# keys.net
KiCad netlist of a schematic drawn in Altium Designer
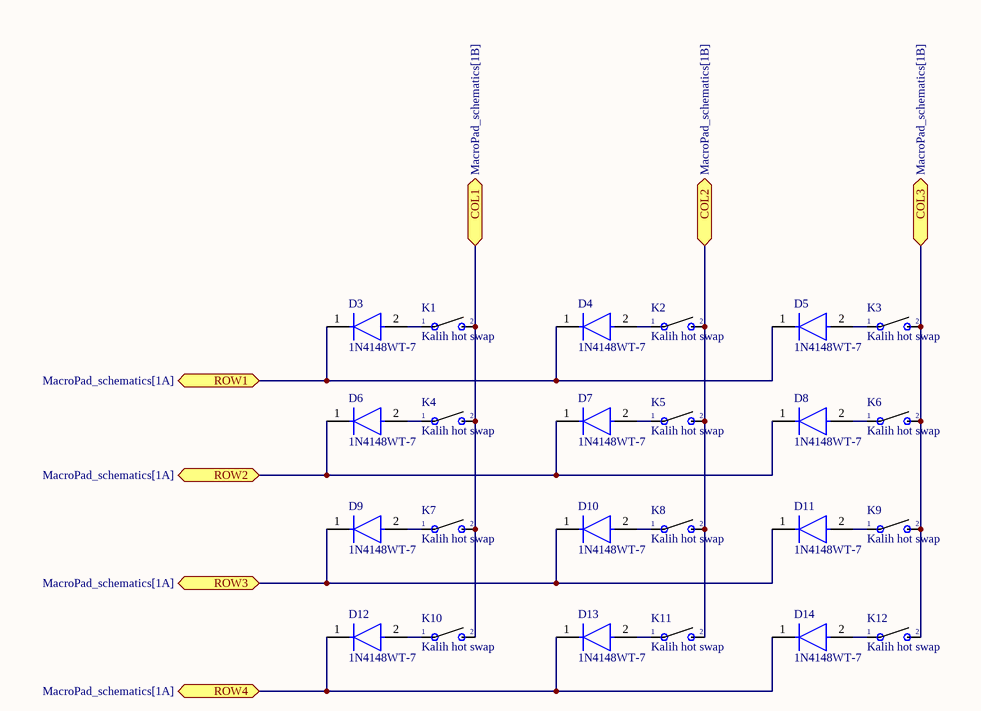
[diagram p0: keys.SchDoc]

(export (version "E")
  (design (tool "Eeschema 10.0.6"))
  (components
    (comp (ref "D3")
      (value "1N4148WT-7")
      (footprint "FP-SOD523-MFG")
      (description "DIODE GEN PURP 80V 125MA SOD523")
      (libsource (lib "Altium Content Vault") (part "d7152d700b627762746794eb795d46e"))
    )
    (comp (ref "D4")
      (value "1N4148WT-7")
      (footprint "FP-SOD523-MFG")
      (description "DIODE GEN PURP 80V 125MA SOD523")
      (libsource (lib "Altium Content Vault") (part "d7152d700b627762746794eb795d46e"))
    )
    (comp (ref "D5")
      (value "1N4148WT-7")
      (footprint "FP-SOD523-MFG")
      (description "DIODE GEN PURP 80V 125MA SOD523")
      (libsource (lib "Altium Content Vault") (part "d7152d700b627762746794eb795d46e"))
    )
    (comp (ref "D6")
      (value "1N4148WT-7")
      (footprint "FP-SOD523-MFG")
      (description "DIODE GEN PURP 80V 125MA SOD523")
      (libsource (lib "Altium Content Vault") (part "d7152d700b627762746794eb795d46e"))
    )
    (comp (ref "D7")
      (value "1N4148WT-7")
      (footprint "FP-SOD523-MFG")
      (description "DIODE GEN PURP 80V 125MA SOD523")
      (libsource (lib "Altium Content Vault") (part "d7152d700b627762746794eb795d46e"))
    )
    (comp (ref "D8")
      (value "1N4148WT-7")
      (footprint "FP-SOD523-MFG")
      (description "DIODE GEN PURP 80V 125MA SOD523")
      (libsource (lib "Altium Content Vault") (part "d7152d700b627762746794eb795d46e"))
    )
    (comp (ref "D9")
      (value "1N4148WT-7")
      (footprint "FP-SOD523-MFG")
      (description "DIODE GEN PURP 80V 125MA SOD523")
      (libsource (lib "Altium Content Vault") (part "d7152d700b627762746794eb795d46e"))
    )
    (comp (ref "D10")
      (value "1N4148WT-7")
      (footprint "FP-SOD523-MFG")
      (description "DIODE GEN PURP 80V 125MA SOD523")
      (libsource (lib "Altium Content Vault") (part "d7152d700b627762746794eb795d46e"))
    )
    (comp (ref "D11")
      (value "1N4148WT-7")
      (footprint "FP-SOD523-MFG")
      (description "DIODE GEN PURP 80V 125MA SOD523")
      (libsource (lib "Altium Content Vault") (part "d7152d700b627762746794eb795d46e"))
    )
    (comp (ref "D12")
      (value "1N4148WT-7")
      (footprint "FP-SOD523-MFG")
      (description "DIODE GEN PURP 80V 125MA SOD523")
      (libsource (lib "Altium Content Vault") (part "d7152d700b627762746794eb795d46e"))
    )
    (comp (ref "D13")
      (value "1N4148WT-7")
      (footprint "FP-SOD523-MFG")
      (description "DIODE GEN PURP 80V 125MA SOD523")
      (libsource (lib "Altium Content Vault") (part "d7152d700b627762746794eb795d46e"))
    )
    (comp (ref "D14")
      (value "1N4148WT-7")
      (footprint "FP-SOD523-MFG")
      (description "DIODE GEN PURP 80V 125MA SOD523")
      (libsource (lib "Altium Content Vault") (part "d7152d700b627762746794eb795d46e"))
    )
    (comp (ref "K1")
      (value "Kalih hot swap")
      (footprint "Kailh_socket_MX_optional_reversible")
      (libsource (lib "MacroPad_schematicsLibrary") (part "Kalih hot swap"))
    )
    (comp (ref "K2")
      (value "Kalih hot swap")
      (footprint "Kailh_socket_MX_optional_reversible")
      (libsource (lib "MacroPad_schematicsLibrary") (part "Kalih hot swap"))
    )
    (comp (ref "K3")
      (value "Kalih hot swap")
      (footprint "Kailh_socket_MX_optional_reversible")
      (libsource (lib "MacroPad_schematicsLibrary") (part "Kalih hot swap"))
    )
    (comp (ref "K4")
      (value "Kalih hot swap")
      (footprint "Kailh_socket_MX_optional_reversible")
      (libsource (lib "MacroPad_schematicsLibrary") (part "Kalih hot swap"))
    )
    (comp (ref "K5")
      (value "Kalih hot swap")
      (footprint "Kailh_socket_MX_optional_reversible")
      (libsource (lib "MacroPad_schematicsLibrary") (part "Kalih hot swap"))
    )
    (comp (ref "K6")
      (value "Kalih hot swap")
      (footprint "Kailh_socket_MX_optional_reversible")
      (libsource (lib "MacroPad_schematicsLibrary") (part "Kalih hot swap"))
    )
    (comp (ref "K7")
      (value "Kalih hot swap")
      (footprint "Kailh_socket_MX_optional_reversible")
      (libsource (lib "MacroPad_schematicsLibrary") (part "Kalih hot swap"))
    )
    (comp (ref "K8")
      (value "Kalih hot swap")
      (footprint "Kailh_socket_MX_optional_reversible")
      (libsource (lib "MacroPad_schematicsLibrary") (part "Kalih hot swap"))
    )
    (comp (ref "K9")
      (value "Kalih hot swap")
      (footprint "Kailh_socket_MX_optional_reversible")
      (libsource (lib "MacroPad_schematicsLibrary") (part "Kalih hot swap"))
    )
    (comp (ref "K10")
      (value "Kalih hot swap")
      (footprint "Kailh_socket_MX_optional_reversible")
      (libsource (lib "MacroPad_schematicsLibrary") (part "Kalih hot swap"))
    )
    (comp (ref "K11")
      (value "Kalih hot swap")
      (footprint "Kailh_socket_MX_optional_reversible")
      (libsource (lib "MacroPad_schematicsLibrary") (part "Kalih hot swap"))
    )
    (comp (ref "K12")
      (value "Kalih hot swap")
      (footprint "Kailh_socket_MX_optional_reversible")
      (libsource (lib "MacroPad_schematicsLibrary") (part "Kalih hot swap"))
    )
  )
  (nets
    (net (code "1") (name "/COL1") (class "Default")
      (node (ref "K1") (pin "2") (pinfunction "2_2") (pintype "passive"))
      (node (ref "K10") (pin "2") (pinfunction "2_2") (pintype "passive"))
      (node (ref "K4") (pin "2") (pinfunction "2_2") (pintype "passive"))
      (node (ref "K7") (pin "2") (pinfunction "2_2") (pintype "passive"))
    )
    (net (code "2") (name "/COL2") (class "Default")
      (node (ref "K11") (pin "2") (pinfunction "2_2") (pintype "passive"))
      (node (ref "K2") (pin "2") (pinfunction "2_2") (pintype "passive"))
      (node (ref "K5") (pin "2") (pinfunction "2_2") (pintype "passive"))
      (node (ref "K8") (pin "2") (pinfunction "2_2") (pintype "passive"))
    )
    (net (code "3") (name "/COL3") (class "Default")
      (node (ref "K12") (pin "2") (pinfunction "2_2") (pintype "passive"))
      (node (ref "K3") (pin "2") (pinfunction "2_2") (pintype "passive"))
      (node (ref "K6") (pin "2") (pinfunction "2_2") (pintype "passive"))
      (node (ref "K9") (pin "2") (pinfunction "2_2") (pintype "passive"))
    )
    (net (code "4") (name "/ROW1") (class "Default")
      (node (ref "D3") (pin "1") (pinfunction "C_1") (pintype "passive"))
      (node (ref "D4") (pin "1") (pinfunction "C_1") (pintype "passive"))
      (node (ref "D5") (pin "1") (pinfunction "C_1") (pintype "passive"))
    )
    (net (code "5") (name "/ROW2") (class "Default")
      (node (ref "D6") (pin "1") (pinfunction "C_1") (pintype "passive"))
      (node (ref "D7") (pin "1") (pinfunction "C_1") (pintype "passive"))
      (node (ref "D8") (pin "1") (pinfunction "C_1") (pintype "passive"))
    )
    (net (code "6") (name "/ROW3") (class "Default")
      (node (ref "D10") (pin "1") (pinfunction "C_1") (pintype "passive"))
      (node (ref "D11") (pin "1") (pinfunction "C_1") (pintype "passive"))
      (node (ref "D9") (pin "1") (pinfunction "C_1") (pintype "passive"))
    )
    (net (code "7") (name "/ROW4") (class "Default")
      (node (ref "D12") (pin "1") (pinfunction "C_1") (pintype "passive"))
      (node (ref "D13") (pin "1") (pinfunction "C_1") (pintype "passive"))
      (node (ref "D14") (pin "1") (pinfunction "C_1") (pintype "passive"))
    )
    (net (code "8") (name "Net-(D3-A)") (class "Default")
      (node (ref "D3") (pin "2") (pinfunction "A_2") (pintype "passive"))
      (node (ref "K1") (pin "1") (pinfunction "1_1") (pintype "passive"))
    )
    (net (code "9") (name "Net-(D4-A)") (class "Default")
      (node (ref "D4") (pin "2") (pinfunction "A_2") (pintype "passive"))
      (node (ref "K2") (pin "1") (pinfunction "1_1") (pintype "passive"))
    )
    (net (code "10") (name "Net-(D5-A)") (class "Default")
      (node (ref "D5") (pin "2") (pinfunction "A_2") (pintype "passive"))
      (node (ref "K3") (pin "1") (pinfunction "1_1") (pintype "passive"))
    )
    (net (code "11") (name "Net-(D6-A)") (class "Default")
      (node (ref "D6") (pin "2") (pinfunction "A_2") (pintype "passive"))
      (node (ref "K4") (pin "1") (pinfunction "1_1") (pintype "passive"))
    )
    (net (code "12") (name "Net-(D7-A)") (class "Default")
      (node (ref "D7") (pin "2") (pinfunction "A_2") (pintype "passive"))
      (node (ref "K5") (pin "1") (pinfunction "1_1") (pintype "passive"))
    )
    (net (code "13") (name "Net-(D8-A)") (class "Default")
      (node (ref "D8") (pin "2") (pinfunction "A_2") (pintype "passive"))
      (node (ref "K6") (pin "1") (pinfunction "1_1") (pintype "passive"))
    )
    (net (code "14") (name "Net-(D9-A)") (class "Default")
      (node (ref "D9") (pin "2") (pinfunction "A_2") (pintype "passive"))
      (node (ref "K7") (pin "1") (pinfunction "1_1") (pintype "passive"))
    )
    (net (code "15") (name "Net-(D10-A)") (class "Default")
      (node (ref "D10") (pin "2") (pinfunction "A_2") (pintype "passive"))
      (node (ref "K8") (pin "1") (pinfunction "1_1") (pintype "passive"))
    )
    (net (code "16") (name "Net-(D11-A)") (class "Default")
      (node (ref "D11") (pin "2") (pinfunction "A_2") (pintype "passive"))
      (node (ref "K9") (pin "1") (pinfunction "1_1") (pintype "passive"))
    )
    (net (code "17") (name "Net-(D12-A)") (class "Default")
      (node (ref "D12") (pin "2") (pinfunction "A_2") (pintype "passive"))
      (node (ref "K10") (pin "1") (pinfunction "1_1") (pintype "passive"))
    )
    (net (code "18") (name "Net-(D13-A)") (class "Default")
      (node (ref "D13") (pin "2") (pinfunction "A_2") (pintype "passive"))
      (node (ref "K11") (pin "1") (pinfunction "1_1") (pintype "passive"))
    )
    (net (code "19") (name "Net-(D14-A)") (class "Default")
      (node (ref "D14") (pin "2") (pinfunction "A_2") (pintype "passive"))
      (node (ref "K12") (pin "1") (pinfunction "1_1") (pintype "passive"))
    )
  )
)
